# schematic.net
KiCad netlist of a schematic drawn in EAGLE
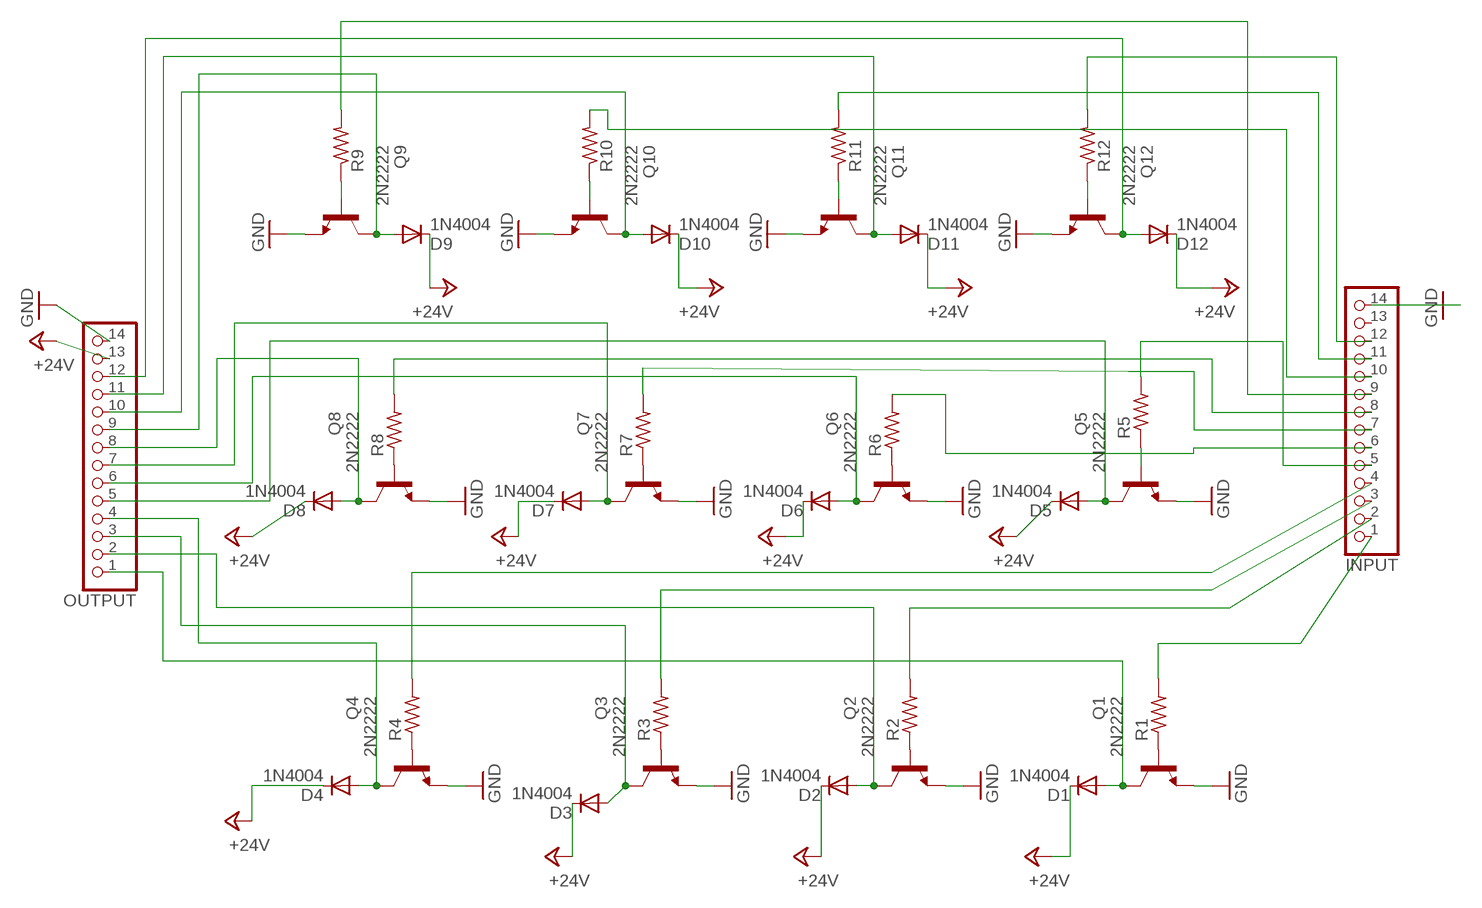
[diagram p0: schematic, sheet 1]

(export (version "E")
  (design (tool "Eeschema 10.0.6"))
  (components
    (comp (ref "D1")
      (value "1N4004")
      (footprint "eagle-import:DO41-10")
      (libsource (lib "eagle-import") (part "1N4004"))
    )
    (comp (ref "D2")
      (value "1N4004")
      (footprint "eagle-import:DO41-10")
      (libsource (lib "eagle-import") (part "1N4004"))
    )
    (comp (ref "D3")
      (value "1N4004")
      (footprint "eagle-import:DO41-10")
      (libsource (lib "eagle-import") (part "1N4004"))
    )
    (comp (ref "D4")
      (value "1N4004")
      (footprint "eagle-import:DO41-10")
      (libsource (lib "eagle-import") (part "1N4004"))
    )
    (comp (ref "D5")
      (value "1N4004")
      (footprint "eagle-import:DO41-10")
      (libsource (lib "eagle-import") (part "1N4004"))
    )
    (comp (ref "D6")
      (value "1N4004")
      (footprint "eagle-import:DO41-10")
      (libsource (lib "eagle-import") (part "1N4004"))
    )
    (comp (ref "D7")
      (value "1N4004")
      (footprint "eagle-import:DO41-10")
      (libsource (lib "eagle-import") (part "1N4004"))
    )
    (comp (ref "D8")
      (value "1N4004")
      (footprint "eagle-import:DO41-10")
      (libsource (lib "eagle-import") (part "1N4004"))
    )
    (comp (ref "D9")
      (value "1N4004")
      (footprint "eagle-import:DO41-10")
      (libsource (lib "eagle-import") (part "1N4004"))
    )
    (comp (ref "D10")
      (value "1N4004")
      (footprint "eagle-import:DO41-10")
      (libsource (lib "eagle-import") (part "1N4004"))
    )
    (comp (ref "D11")
      (value "1N4004")
      (footprint "eagle-import:DO41-10")
      (libsource (lib "eagle-import") (part "1N4004"))
    )
    (comp (ref "D12")
      (value "1N4004")
      (footprint "eagle-import:DO41-10")
      (libsource (lib "eagle-import") (part "1N4004"))
    )
    (comp (ref "INPUT")
      (value "PINHD-1X14")
      (footprint "eagle-import:1X14")
      (libsource (lib "eagle-import") (part "PINHD-1X14"))
    )
    (comp (ref "OUTPUT")
      (value "PINHD-1X14")
      (footprint "eagle-import:1X14")
      (libsource (lib "eagle-import") (part "PINHD-1X14"))
    )
    (comp (ref "Q1")
      (value "2N2222")
      (footprint "eagle-import:TO92-EBC-OVAL")
      (fields (field (name "MF") "FAIRCHILD SEMICONDUCTOR") (field (name "MPN") "PN2222ATF"))
      (libsource (lib "eagle-import") (part "2N2222"))
    )
    (comp (ref "Q2")
      (value "2N2222")
      (footprint "eagle-import:TO92-EBC-OVAL")
      (fields (field (name "MF") "FAIRCHILD SEMICONDUCTOR") (field (name "MPN") "PN2222ATF"))
      (libsource (lib "eagle-import") (part "2N2222"))
    )
    (comp (ref "Q3")
      (value "2N2222")
      (footprint "eagle-import:TO92-EBC-OVAL")
      (fields (field (name "MF") "FAIRCHILD SEMICONDUCTOR") (field (name "MPN") "PN2222ATF"))
      (libsource (lib "eagle-import") (part "2N2222"))
    )
    (comp (ref "Q4")
      (value "2N2222")
      (footprint "eagle-import:TO92-EBC-OVAL")
      (fields (field (name "MF") "FAIRCHILD SEMICONDUCTOR") (field (name "MPN") "PN2222ATF"))
      (libsource (lib "eagle-import") (part "2N2222"))
    )
    (comp (ref "Q5")
      (value "2N2222")
      (footprint "eagle-import:TO92-EBC-OVAL")
      (fields (field (name "MF") "FAIRCHILD SEMICONDUCTOR") (field (name "MPN") "PN2222ATF"))
      (libsource (lib "eagle-import") (part "2N2222"))
    )
    (comp (ref "Q6")
      (value "2N2222")
      (footprint "eagle-import:TO92-EBC-OVAL")
      (fields (field (name "MF") "FAIRCHILD SEMICONDUCTOR") (field (name "MPN") "PN2222ATF"))
      (libsource (lib "eagle-import") (part "2N2222"))
    )
    (comp (ref "Q7")
      (value "2N2222")
      (footprint "eagle-import:TO92-EBC-OVAL")
      (fields (field (name "MF") "FAIRCHILD SEMICONDUCTOR") (field (name "MPN") "PN2222ATF"))
      (libsource (lib "eagle-import") (part "2N2222"))
    )
    (comp (ref "Q8")
      (value "2N2222")
      (footprint "eagle-import:TO92-EBC-OVAL")
      (fields (field (name "MF") "FAIRCHILD SEMICONDUCTOR") (field (name "MPN") "PN2222ATF"))
      (libsource (lib "eagle-import") (part "2N2222"))
    )
    (comp (ref "Q9")
      (value "2N2222")
      (footprint "eagle-import:TO92-EBC-OVAL")
      (fields (field (name "MF") "FAIRCHILD SEMICONDUCTOR") (field (name "MPN") "PN2222ATF"))
      (libsource (lib "eagle-import") (part "2N2222"))
    )
    (comp (ref "Q10")
      (value "2N2222")
      (footprint "eagle-import:TO92-EBC-OVAL")
      (fields (field (name "MF") "FAIRCHILD SEMICONDUCTOR") (field (name "MPN") "PN2222ATF"))
      (libsource (lib "eagle-import") (part "2N2222"))
    )
    (comp (ref "Q11")
      (value "2N2222")
      (footprint "eagle-import:TO92-EBC-OVAL")
      (fields (field (name "MF") "FAIRCHILD SEMICONDUCTOR") (field (name "MPN") "PN2222ATF"))
      (libsource (lib "eagle-import") (part "2N2222"))
    )
    (comp (ref "Q12")
      (value "2N2222")
      (footprint "eagle-import:TO92-EBC-OVAL")
      (fields (field (name "MF") "FAIRCHILD SEMICONDUCTOR") (field (name "MPN") "PN2222ATF"))
      (libsource (lib "eagle-import") (part "2N2222"))
    )
    (comp (ref "R1")
      (value "R-US_0309/12")
      (footprint "eagle-import:0309_12")
      (libsource (lib "eagle-import") (part "R-US_0309/12"))
    )
    (comp (ref "R2")
      (value "R-US_0309/12")
      (footprint "eagle-import:0309_12")
      (libsource (lib "eagle-import") (part "R-US_0309/12"))
    )
    (comp (ref "R3")
      (value "R-US_0309/12")
      (footprint "eagle-import:0309_12")
      (libsource (lib "eagle-import") (part "R-US_0309/12"))
    )
    (comp (ref "R4")
      (value "R-US_0309/12")
      (footprint "eagle-import:0309_12")
      (libsource (lib "eagle-import") (part "R-US_0309/12"))
    )
    (comp (ref "R5")
      (value "R-US_0309/12")
      (footprint "eagle-import:0309_12")
      (libsource (lib "eagle-import") (part "R-US_0309/12"))
    )
    (comp (ref "R6")
      (value "R-US_0309/12")
      (footprint "eagle-import:0309_12")
      (libsource (lib "eagle-import") (part "R-US_0309/12"))
    )
    (comp (ref "R7")
      (value "R-US_0309/12")
      (footprint "eagle-import:0309_12")
      (libsource (lib "eagle-import") (part "R-US_0309/12"))
    )
    (comp (ref "R8")
      (value "R-US_0309/12")
      (footprint "eagle-import:0309_12")
      (libsource (lib "eagle-import") (part "R-US_0309/12"))
    )
    (comp (ref "R9")
      (value "R-US_0309/12")
      (footprint "eagle-import:0309_12")
      (libsource (lib "eagle-import") (part "R-US_0309/12"))
    )
    (comp (ref "R10")
      (value "R-US_0309/12")
      (footprint "eagle-import:0309_12")
      (libsource (lib "eagle-import") (part "R-US_0309/12"))
    )
    (comp (ref "R11")
      (value "R-US_0309/12")
      (footprint "eagle-import:0309_12")
      (libsource (lib "eagle-import") (part "R-US_0309/12"))
    )
    (comp (ref "R12")
      (value "R-US_0309/12")
      (footprint "eagle-import:0309_12")
      (libsource (lib "eagle-import") (part "R-US_0309/12"))
    )
  )
  (nets
    (net (code "1") (name "+24V") (class "Default")
      (node (ref "D1") (pin "C") (pinfunction "C_C") (pintype "passive"))
      (node (ref "D10") (pin "C") (pinfunction "C_C") (pintype "passive"))
      (node (ref "D11") (pin "C") (pinfunction "C_C") (pintype "passive"))
      (node (ref "D12") (pin "C") (pinfunction "C_C") (pintype "passive"))
      (node (ref "D2") (pin "C") (pinfunction "C_C") (pintype "passive"))
      (node (ref "D3") (pin "C") (pinfunction "C_C") (pintype "passive"))
      (node (ref "D4") (pin "C") (pinfunction "C_C") (pintype "passive"))
      (node (ref "D5") (pin "C") (pinfunction "C_C") (pintype "passive"))
      (node (ref "D6") (pin "C") (pinfunction "C_C") (pintype "passive"))
      (node (ref "D7") (pin "C") (pinfunction "C_C") (pintype "passive"))
      (node (ref "D8") (pin "C") (pinfunction "C_C") (pintype "passive"))
      (node (ref "D9") (pin "C") (pinfunction "C_C") (pintype "passive"))
      (node (ref "OUTPUT") (pin "13") (pinfunction "13_13") (pintype "passive"))
    )
    (net (code "2") (name "GND") (class "Default")
      (node (ref "INPUT") (pin "14") (pinfunction "14_14") (pintype "passive"))
      (node (ref "OUTPUT") (pin "14") (pinfunction "14_14") (pintype "passive"))
      (node (ref "Q1") (pin "E") (pinfunction "E_E") (pintype "passive"))
      (node (ref "Q10") (pin "E") (pinfunction "E_E") (pintype "passive"))
      (node (ref "Q11") (pin "E") (pinfunction "E_E") (pintype "passive"))
      (node (ref "Q12") (pin "E") (pinfunction "E_E") (pintype "passive"))
      (node (ref "Q2") (pin "E") (pinfunction "E_E") (pintype "passive"))
      (node (ref "Q3") (pin "E") (pinfunction "E_E") (pintype "passive"))
      (node (ref "Q4") (pin "E") (pinfunction "E_E") (pintype "passive"))
      (node (ref "Q5") (pin "E") (pinfunction "E_E") (pintype "passive"))
      (node (ref "Q6") (pin "E") (pinfunction "E_E") (pintype "passive"))
      (node (ref "Q7") (pin "E") (pinfunction "E_E") (pintype "passive"))
      (node (ref "Q8") (pin "E") (pinfunction "E_E") (pintype "passive"))
      (node (ref "Q9") (pin "E") (pinfunction "E_E") (pintype "passive"))
    )
    (net (code "3") (name "Net-(D1-PadA)") (class "Default")
      (node (ref "D1") (pin "A") (pinfunction "A_A") (pintype "passive"))
      (node (ref "OUTPUT") (pin "1") (pinfunction "1_1") (pintype "passive"))
      (node (ref "Q1") (pin "C") (pinfunction "C_C") (pintype "passive"))
    )
    (net (code "4") (name "Net-(D2-PadA)") (class "Default")
      (node (ref "D2") (pin "A") (pinfunction "A_A") (pintype "passive"))
      (node (ref "OUTPUT") (pin "2") (pinfunction "2_2") (pintype "passive"))
      (node (ref "Q2") (pin "C") (pinfunction "C_C") (pintype "passive"))
    )
    (net (code "5") (name "Net-(D3-PadA)") (class "Default")
      (node (ref "D3") (pin "A") (pinfunction "A_A") (pintype "passive"))
      (node (ref "OUTPUT") (pin "3") (pinfunction "3_3") (pintype "passive"))
      (node (ref "Q3") (pin "C") (pinfunction "C_C") (pintype "passive"))
    )
    (net (code "6") (name "Net-(D4-PadA)") (class "Default")
      (node (ref "D4") (pin "A") (pinfunction "A_A") (pintype "passive"))
      (node (ref "OUTPUT") (pin "4") (pinfunction "4_4") (pintype "passive"))
      (node (ref "Q4") (pin "C") (pinfunction "C_C") (pintype "passive"))
    )
    (net (code "7") (name "Net-(D5-PadA)") (class "Default")
      (node (ref "D5") (pin "A") (pinfunction "A_A") (pintype "passive"))
      (node (ref "OUTPUT") (pin "5") (pinfunction "5_5") (pintype "passive"))
      (node (ref "Q5") (pin "C") (pinfunction "C_C") (pintype "passive"))
    )
    (net (code "8") (name "Net-(D6-PadA)") (class "Default")
      (node (ref "D6") (pin "A") (pinfunction "A_A") (pintype "passive"))
      (node (ref "OUTPUT") (pin "6") (pinfunction "6_6") (pintype "passive"))
      (node (ref "Q6") (pin "C") (pinfunction "C_C") (pintype "passive"))
    )
    (net (code "9") (name "Net-(D7-PadA)") (class "Default")
      (node (ref "D7") (pin "A") (pinfunction "A_A") (pintype "passive"))
      (node (ref "OUTPUT") (pin "7") (pinfunction "7_7") (pintype "passive"))
      (node (ref "Q7") (pin "C") (pinfunction "C_C") (pintype "passive"))
    )
    (net (code "10") (name "Net-(D8-PadA)") (class "Default")
      (node (ref "D8") (pin "A") (pinfunction "A_A") (pintype "passive"))
      (node (ref "OUTPUT") (pin "8") (pinfunction "8_8") (pintype "passive"))
      (node (ref "Q8") (pin "C") (pinfunction "C_C") (pintype "passive"))
    )
    (net (code "11") (name "Net-(D9-PadA)") (class "Default")
      (node (ref "D9") (pin "A") (pinfunction "A_A") (pintype "passive"))
      (node (ref "OUTPUT") (pin "9") (pinfunction "9_9") (pintype "passive"))
      (node (ref "Q9") (pin "C") (pinfunction "C_C") (pintype "passive"))
    )
    (net (code "12") (name "Net-(D10-PadA)") (class "Default")
      (node (ref "D10") (pin "A") (pinfunction "A_A") (pintype "passive"))
      (node (ref "OUTPUT") (pin "10") (pinfunction "10_10") (pintype "passive"))
      (node (ref "Q10") (pin "C") (pinfunction "C_C") (pintype "passive"))
    )
    (net (code "13") (name "Net-(D11-PadA)") (class "Default")
      (node (ref "D11") (pin "A") (pinfunction "A_A") (pintype "passive"))
      (node (ref "OUTPUT") (pin "11") (pinfunction "11_11") (pintype "passive"))
      (node (ref "Q11") (pin "C") (pinfunction "C_C") (pintype "passive"))
    )
    (net (code "14") (name "Net-(D12-PadA)") (class "Default")
      (node (ref "D12") (pin "A") (pinfunction "A_A") (pintype "passive"))
      (node (ref "OUTPUT") (pin "12") (pinfunction "12_12") (pintype "passive"))
      (node (ref "Q12") (pin "C") (pinfunction "C_C") (pintype "passive"))
    )
    (net (code "15") (name "Net-(INPUT-Pad1)") (class "Default")
      (node (ref "INPUT") (pin "1") (pinfunction "1_1") (pintype "passive"))
      (node (ref "R1") (pin "2") (pinfunction "2_2") (pintype "passive"))
    )
    (net (code "16") (name "Net-(INPUT-Pad2)") (class "Default")
      (node (ref "INPUT") (pin "2") (pinfunction "2_2") (pintype "passive"))
      (node (ref "R2") (pin "2") (pinfunction "2_2") (pintype "passive"))
    )
    (net (code "17") (name "Net-(INPUT-Pad3)") (class "Default")
      (node (ref "INPUT") (pin "3") (pinfunction "3_3") (pintype "passive"))
      (node (ref "R3") (pin "2") (pinfunction "2_2") (pintype "passive"))
    )
    (net (code "18") (name "Net-(INPUT-Pad4)") (class "Default")
      (node (ref "INPUT") (pin "4") (pinfunction "4_4") (pintype "passive"))
      (node (ref "R4") (pin "2") (pinfunction "2_2") (pintype "passive"))
    )
    (net (code "19") (name "Net-(INPUT-Pad5)") (class "Default")
      (node (ref "INPUT") (pin "5") (pinfunction "5_5") (pintype "passive"))
      (node (ref "R5") (pin "2") (pinfunction "2_2") (pintype "passive"))
    )
    (net (code "20") (name "Net-(INPUT-Pad6)") (class "Default")
      (node (ref "INPUT") (pin "6") (pinfunction "6_6") (pintype "passive"))
      (node (ref "R6") (pin "2") (pinfunction "2_2") (pintype "passive"))
    )
    (net (code "21") (name "Net-(INPUT-Pad7)") (class "Default")
      (node (ref "INPUT") (pin "7") (pinfunction "7_7") (pintype "passive"))
      (node (ref "R7") (pin "2") (pinfunction "2_2") (pintype "passive"))
    )
    (net (code "22") (name "Net-(INPUT-Pad8)") (class "Default")
      (node (ref "INPUT") (pin "8") (pinfunction "8_8") (pintype "passive"))
      (node (ref "R8") (pin "2") (pinfunction "2_2") (pintype "passive"))
    )
    (net (code "23") (name "Net-(INPUT-Pad9)") (class "Default")
      (node (ref "INPUT") (pin "9") (pinfunction "9_9") (pintype "passive"))
      (node (ref "R9") (pin "2") (pinfunction "2_2") (pintype "passive"))
    )
    (net (code "24") (name "Net-(INPUT-Pad10)") (class "Default")
      (node (ref "INPUT") (pin "10") (pinfunction "10_10") (pintype "passive"))
      (node (ref "R10") (pin "2") (pinfunction "2_2") (pintype "passive"))
    )
    (net (code "25") (name "Net-(INPUT-Pad11)") (class "Default")
      (node (ref "INPUT") (pin "11") (pinfunction "11_11") (pintype "passive"))
      (node (ref "R11") (pin "2") (pinfunction "2_2") (pintype "passive"))
    )
    (net (code "26") (name "Net-(INPUT-Pad12)") (class "Default")
      (node (ref "INPUT") (pin "12") (pinfunction "12_12") (pintype "passive"))
      (node (ref "R12") (pin "2") (pinfunction "2_2") (pintype "passive"))
    )
    (net (code "27") (name "Net-(Q1-PadB)") (class "Default")
      (node (ref "Q1") (pin "B") (pinfunction "B_B") (pintype "passive"))
      (node (ref "R1") (pin "1") (pinfunction "1_1") (pintype "passive"))
    )
    (net (code "28") (name "Net-(Q2-PadB)") (class "Default")
      (node (ref "Q2") (pin "B") (pinfunction "B_B") (pintype "passive"))
      (node (ref "R2") (pin "1") (pinfunction "1_1") (pintype "passive"))
    )
    (net (code "29") (name "Net-(Q3-PadB)") (class "Default")
      (node (ref "Q3") (pin "B") (pinfunction "B_B") (pintype "passive"))
      (node (ref "R3") (pin "1") (pinfunction "1_1") (pintype "passive"))
    )
    (net (code "30") (name "Net-(Q4-PadB)") (class "Default")
      (node (ref "Q4") (pin "B") (pinfunction "B_B") (pintype "passive"))
      (node (ref "R4") (pin "1") (pinfunction "1_1") (pintype "passive"))
    )
    (net (code "31") (name "Net-(Q5-PadB)") (class "Default")
      (node (ref "Q5") (pin "B") (pinfunction "B_B") (pintype "passive"))
      (node (ref "R5") (pin "1") (pinfunction "1_1") (pintype "passive"))
    )
    (net (code "32") (name "Net-(Q6-PadB)") (class "Default")
      (node (ref "Q6") (pin "B") (pinfunction "B_B") (pintype "passive"))
      (node (ref "R6") (pin "1") (pinfunction "1_1") (pintype "passive"))
    )
    (net (code "33") (name "Net-(Q7-PadB)") (class "Default")
      (node (ref "Q7") (pin "B") (pinfunction "B_B") (pintype "passive"))
      (node (ref "R7") (pin "1") (pinfunction "1_1") (pintype "passive"))
    )
    (net (code "34") (name "Net-(Q8-PadB)") (class "Default")
      (node (ref "Q8") (pin "B") (pinfunction "B_B") (pintype "passive"))
      (node (ref "R8") (pin "1") (pinfunction "1_1") (pintype "passive"))
    )
    (net (code "35") (name "Net-(Q9-PadB)") (class "Default")
      (node (ref "Q9") (pin "B") (pinfunction "B_B") (pintype "passive"))
      (node (ref "R9") (pin "1") (pinfunction "1_1") (pintype "passive"))
    )
    (net (code "36") (name "Net-(Q10-PadB)") (class "Default")
      (node (ref "Q10") (pin "B") (pinfunction "B_B") (pintype "passive"))
      (node (ref "R10") (pin "1") (pinfunction "1_1") (pintype "passive"))
    )
    (net (code "37") (name "Net-(Q11-PadB)") (class "Default")
      (node (ref "Q11") (pin "B") (pinfunction "B_B") (pintype "passive"))
      (node (ref "R11") (pin "1") (pinfunction "1_1") (pintype "passive"))
    )
    (net (code "38") (name "Net-(Q12-PadB)") (class "Default")
      (node (ref "Q12") (pin "B") (pinfunction "B_B") (pintype "passive"))
      (node (ref "R12") (pin "1") (pinfunction "1_1") (pintype "passive"))
    )
    (net (code "39") (name "unconnected-(INPUT-Pad13)") (class "Default")
      (node (ref "INPUT") (pin "13") (pinfunction "13_13") (pintype "passive"))
    )
  )
)
